# NOR_1_1.net
KiCad netlist of a schematic drawn in EAGLE
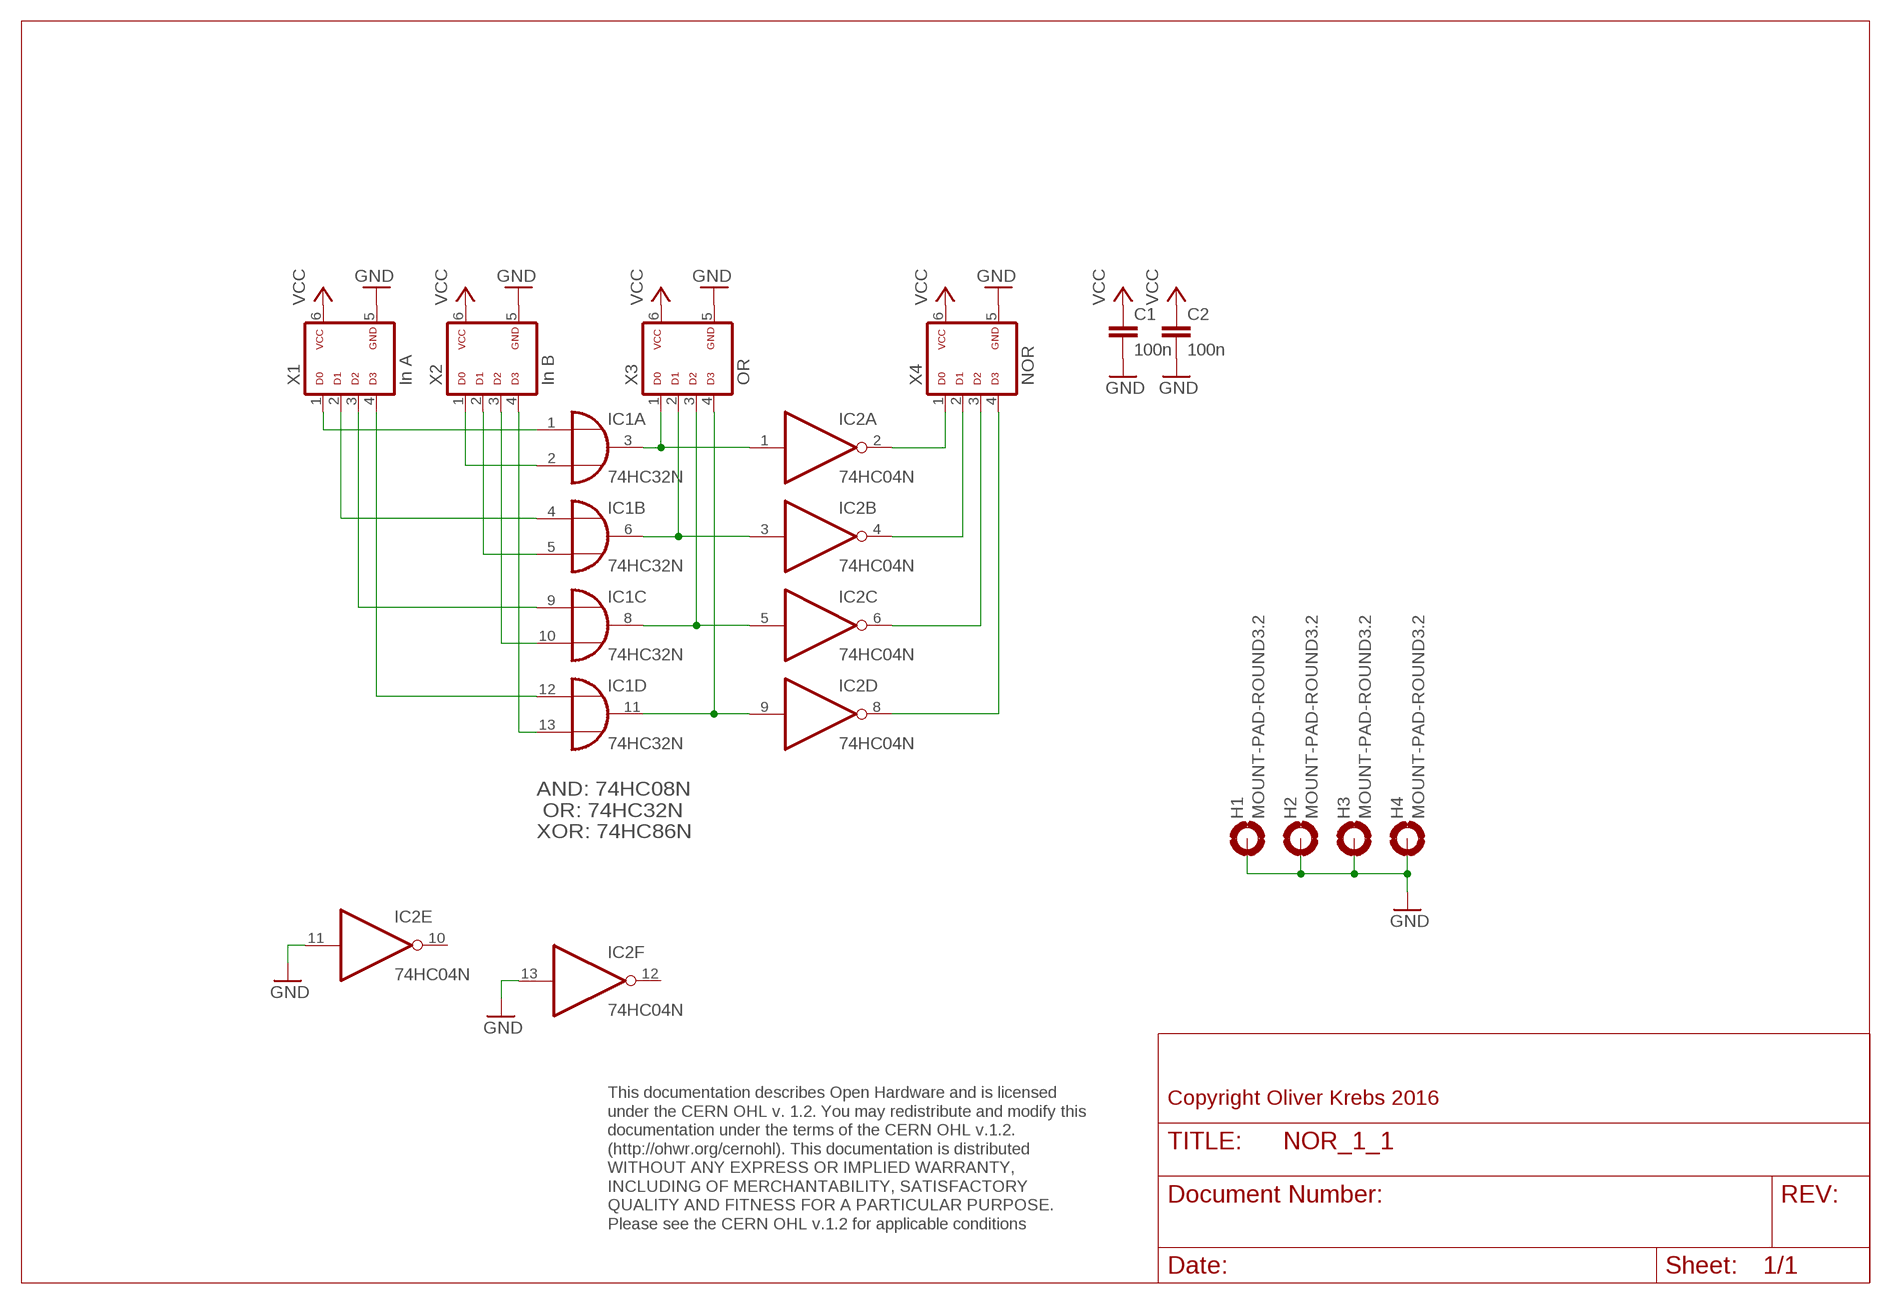
[diagram p0: schematic, sheet 1]

(export (version "E")
  (design (tool "Eeschema 10.0.6"))
  (components
    (comp (ref "C1")
      (value "100n")
      (footprint "eagle-import:C050-025X075")
      (libsource (lib "eagle-import") (part "C-EU050-025X075"))
    )
    (comp (ref "C2")
      (value "100n")
      (footprint "eagle-import:C050-025X075")
      (libsource (lib "eagle-import") (part "C-EU050-025X075"))
    )
    (comp (ref "H1")
      (value "MOUNT-PAD-ROUND3.2")
      (footprint "eagle-import:3,2-PAD")
      (libsource (lib "eagle-import") (part "MOUNT-PAD-ROUND3.2"))
    )
    (comp (ref "H2")
      (value "MOUNT-PAD-ROUND3.2")
      (footprint "eagle-import:3,2-PAD")
      (libsource (lib "eagle-import") (part "MOUNT-PAD-ROUND3.2"))
    )
    (comp (ref "H3")
      (value "MOUNT-PAD-ROUND3.2")
      (footprint "eagle-import:3,2-PAD")
      (libsource (lib "eagle-import") (part "MOUNT-PAD-ROUND3.2"))
    )
    (comp (ref "H4")
      (value "MOUNT-PAD-ROUND3.2")
      (footprint "eagle-import:3,2-PAD")
      (libsource (lib "eagle-import") (part "MOUNT-PAD-ROUND3.2"))
    )
    (comp (ref "IC1")
      (value "74HC32N")
      (footprint "eagle-import:DIL14")
      (libsource (lib "eagle-import") (part "7432NHC"))
    )
    (comp (ref "IC2")
      (value "74HC04N")
      (footprint "eagle-import:DIL14")
      (libsource (lib "eagle-import") (part "7404NHC"))
    )
    (comp (ref "X1")
      (value "In A")
      (footprint "eagle-import:ML-6")
      (libsource (lib "eagle-import") (part "ML6D"))
    )
    (comp (ref "X2")
      (value "In B")
      (footprint "eagle-import:ML-6")
      (libsource (lib "eagle-import") (part "ML6D"))
    )
    (comp (ref "X3")
      (value "OR")
      (footprint "eagle-import:ML-6")
      (libsource (lib "eagle-import") (part "ML6D"))
    )
    (comp (ref "X4")
      (value "NOR")
      (footprint "eagle-import:ML-6")
      (libsource (lib "eagle-import") (part "ML6D"))
    )
  )
  (nets
    (net (code "1") (name "GND") (class "Default")
      (node (ref "C1") (pin "2") (pinfunction "2_2") (pintype "passive"))
      (node (ref "C2") (pin "2") (pinfunction "2_2") (pintype "passive"))
      (node (ref "H1") (pin "B3,2") (pinfunction "MOUNT_B3,2") (pintype "passive"))
      (node (ref "H2") (pin "B3,2") (pinfunction "MOUNT_B3,2") (pintype "passive"))
      (node (ref "H3") (pin "B3,2") (pinfunction "MOUNT_B3,2") (pintype "passive"))
      (node (ref "H4") (pin "B3,2") (pinfunction "MOUNT_B3,2") (pintype "passive"))
      (node (ref "IC2") (pin "11") (pinfunction "I_11") (pintype "input"))
      (node (ref "IC2") (pin "13") (pinfunction "I_13") (pintype "input"))
      (node (ref "X1") (pin "5") (pinfunction "5_5") (pintype "passive"))
      (node (ref "X2") (pin "5") (pinfunction "5_5") (pintype "passive"))
      (node (ref "X3") (pin "5") (pinfunction "5_5") (pintype "passive"))
      (node (ref "X4") (pin "5") (pinfunction "5_5") (pintype "passive"))
    )
    (net (code "2") (name "Net-(IC1A-I0)") (class "Default")
      (node (ref "IC1") (pin "1") (pinfunction "I0_1") (pintype "input"))
      (node (ref "X1") (pin "1") (pinfunction "1_1") (pintype "passive"))
    )
    (net (code "3") (name "Net-(IC1A-I1)") (class "Default")
      (node (ref "IC1") (pin "2") (pinfunction "I1_2") (pintype "input"))
      (node (ref "X2") (pin "1") (pinfunction "1_1") (pintype "passive"))
    )
    (net (code "4") (name "Net-(IC1A-O)") (class "Default")
      (node (ref "IC1") (pin "3") (pinfunction "O_3") (pintype "output"))
      (node (ref "IC2") (pin "1") (pinfunction "I_1") (pintype "input"))
      (node (ref "X3") (pin "1") (pinfunction "1_1") (pintype "passive"))
    )
    (net (code "5") (name "Net-(IC1B-I0)") (class "Default")
      (node (ref "IC1") (pin "4") (pinfunction "I0_4") (pintype "input"))
      (node (ref "X1") (pin "2") (pinfunction "2_2") (pintype "passive"))
    )
    (net (code "6") (name "Net-(IC1B-I1)") (class "Default")
      (node (ref "IC1") (pin "5") (pinfunction "I1_5") (pintype "input"))
      (node (ref "X2") (pin "2") (pinfunction "2_2") (pintype "passive"))
    )
    (net (code "7") (name "Net-(IC1B-O)") (class "Default")
      (node (ref "IC1") (pin "6") (pinfunction "O_6") (pintype "output"))
      (node (ref "IC2") (pin "3") (pinfunction "I_3") (pintype "input"))
      (node (ref "X3") (pin "2") (pinfunction "2_2") (pintype "passive"))
    )
    (net (code "8") (name "Net-(IC1C-I0)") (class "Default")
      (node (ref "IC1") (pin "9") (pinfunction "I0_9") (pintype "input"))
      (node (ref "X1") (pin "3") (pinfunction "3_3") (pintype "passive"))
    )
    (net (code "9") (name "Net-(IC1C-I1)") (class "Default")
      (node (ref "IC1") (pin "10") (pinfunction "I1_10") (pintype "input"))
      (node (ref "X2") (pin "3") (pinfunction "3_3") (pintype "passive"))
    )
    (net (code "10") (name "Net-(IC1C-O)") (class "Default")
      (node (ref "IC1") (pin "8") (pinfunction "O_8") (pintype "output"))
      (node (ref "IC2") (pin "5") (pinfunction "I_5") (pintype "input"))
      (node (ref "X3") (pin "3") (pinfunction "3_3") (pintype "passive"))
    )
    (net (code "11") (name "Net-(IC1D-I0)") (class "Default")
      (node (ref "IC1") (pin "12") (pinfunction "I0_12") (pintype "input"))
      (node (ref "X1") (pin "4") (pinfunction "4_4") (pintype "passive"))
    )
    (net (code "12") (name "Net-(IC1D-I1)") (class "Default")
      (node (ref "IC1") (pin "13") (pinfunction "I1_13") (pintype "input"))
      (node (ref "X2") (pin "4") (pinfunction "4_4") (pintype "passive"))
    )
    (net (code "13") (name "Net-(IC1D-O)") (class "Default")
      (node (ref "IC1") (pin "11") (pinfunction "O_11") (pintype "output"))
      (node (ref "IC2") (pin "9") (pinfunction "I_9") (pintype "input"))
      (node (ref "X3") (pin "4") (pinfunction "4_4") (pintype "passive"))
    )
    (net (code "14") (name "Net-(IC2A-O)") (class "Default")
      (node (ref "IC2") (pin "2") (pinfunction "O_2") (pintype "output"))
      (node (ref "X4") (pin "1") (pinfunction "1_1") (pintype "passive"))
    )
    (net (code "15") (name "Net-(IC2B-O)") (class "Default")
      (node (ref "IC2") (pin "4") (pinfunction "O_4") (pintype "output"))
      (node (ref "X4") (pin "2") (pinfunction "2_2") (pintype "passive"))
    )
    (net (code "16") (name "Net-(IC2C-O)") (class "Default")
      (node (ref "IC2") (pin "6") (pinfunction "O_6") (pintype "output"))
      (node (ref "X4") (pin "3") (pinfunction "3_3") (pintype "passive"))
    )
    (net (code "17") (name "Net-(IC2D-O)") (class "Default")
      (node (ref "IC2") (pin "8") (pinfunction "O_8") (pintype "output"))
      (node (ref "X4") (pin "4") (pinfunction "4_4") (pintype "passive"))
    )
    (net (code "18") (name "VCC") (class "Default")
      (node (ref "C1") (pin "1") (pinfunction "1_1") (pintype "passive"))
      (node (ref "C2") (pin "1") (pinfunction "1_1") (pintype "passive"))
      (node (ref "X1") (pin "6") (pinfunction "6_6") (pintype "passive"))
      (node (ref "X2") (pin "6") (pinfunction "6_6") (pintype "passive"))
      (node (ref "X3") (pin "6") (pinfunction "6_6") (pintype "passive"))
      (node (ref "X4") (pin "6") (pinfunction "6_6") (pintype "passive"))
    )
    (net (code "19") (name "unconnected-(IC2E-O-Pad10)") (class "Default")
      (node (ref "IC2") (pin "10") (pinfunction "O_10") (pintype "output"))
    )
    (net (code "20") (name "unconnected-(IC2F-O-Pad12)") (class "Default")
      (node (ref "IC2") (pin "12") (pinfunction "O_12") (pintype "output"))
    )
  )
)
